# 02_FPGA-jtag.net
KiCad netlist of a schematic drawn in Altium Designer
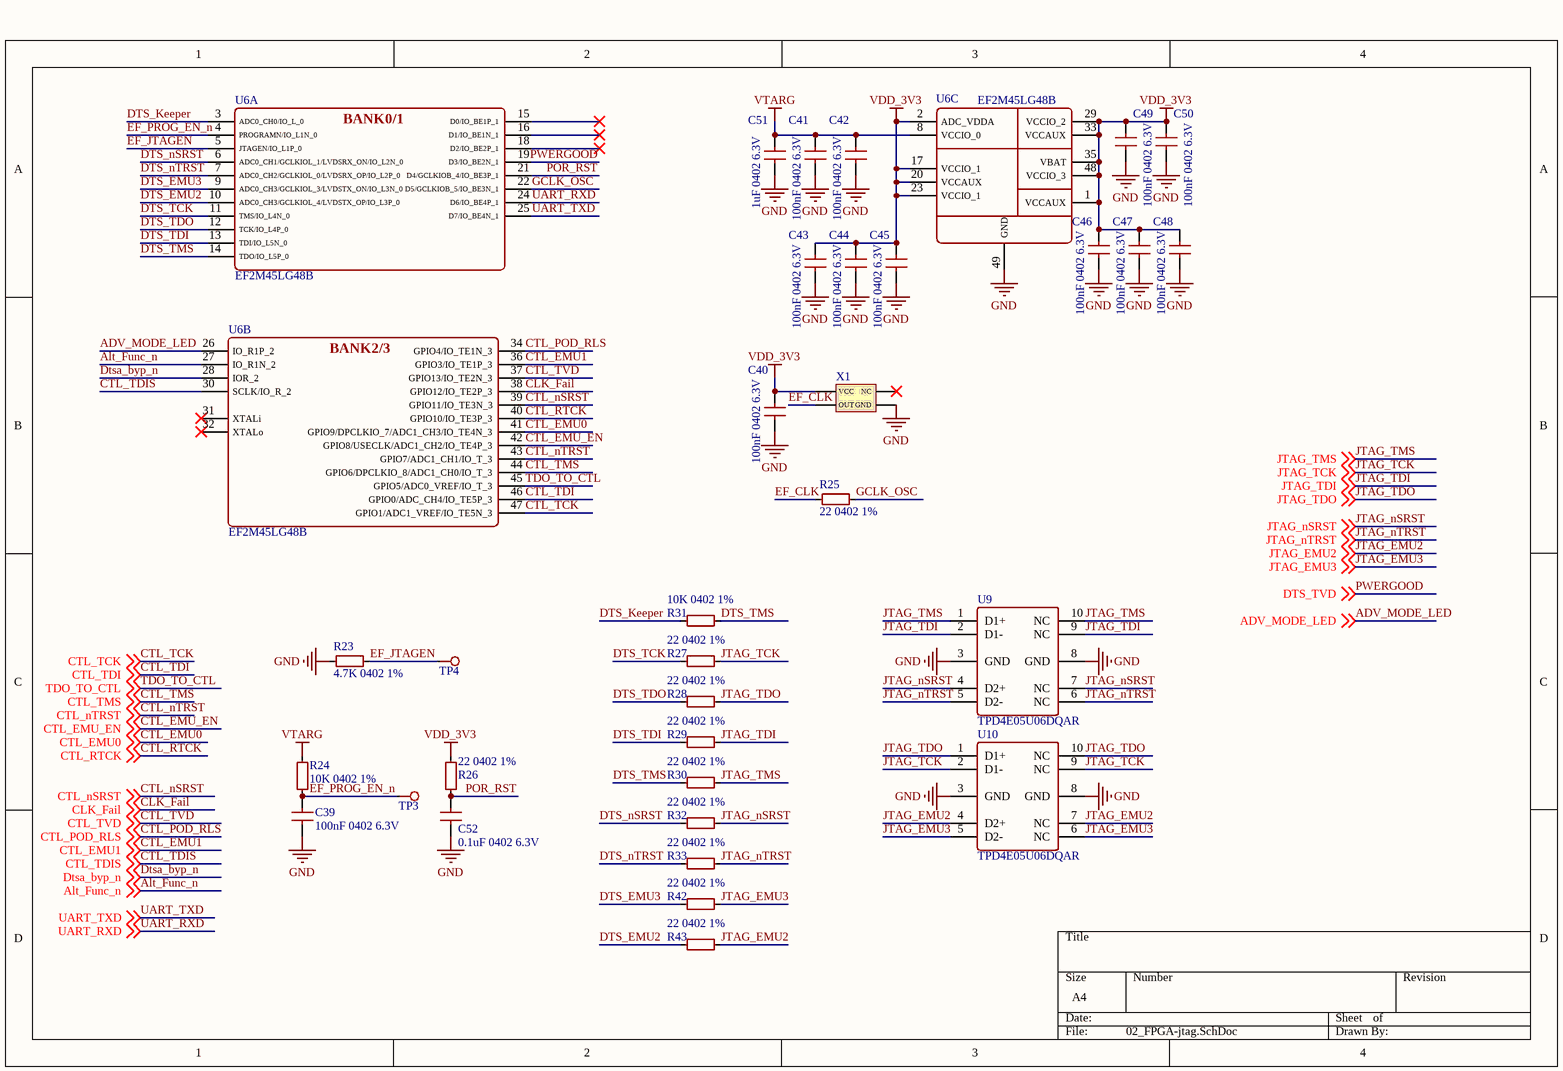
[diagram p0: 02_FPGA-jtag.SchDoc]

(export (version "E")
  (design (tool "Eeschema 10.0.6"))
  (components
    (comp (ref "C39")
      (value "100nF 0402 6.3V")
      (footprint "C_0402_1005Metric")
      (description "Unpolarized capacitor")
      (libsource (lib "FPGA_VGA") (part "C"))
    )
    (comp (ref "C40")
      (value "100nF 0402 6.3V")
      (footprint "C_0402_1005Metric")
      (description "Unpolarized capacitor")
      (libsource (lib "FPGA_VGA") (part "C"))
    )
    (comp (ref "C41")
      (value "100nF 0402 6.3V")
      (footprint "C_0402_1005Metric")
      (description "Unpolarized capacitor")
      (libsource (lib "FPGA_VGA") (part "C"))
    )
    (comp (ref "C42")
      (value "100nF 0402 6.3V")
      (footprint "C_0402_1005Metric")
      (description "Unpolarized capacitor")
      (libsource (lib "FPGA_VGA") (part "C"))
    )
    (comp (ref "C43")
      (value "100nF 0402 6.3V")
      (footprint "C_0402_1005Metric")
      (description "Unpolarized capacitor")
      (libsource (lib "FPGA_VGA") (part "C"))
    )
    (comp (ref "C44")
      (value "100nF 0402 6.3V")
      (footprint "C_0402_1005Metric")
      (description "Unpolarized capacitor")
      (libsource (lib "FPGA_VGA") (part "C"))
    )
    (comp (ref "C45")
      (value "100nF 0402 6.3V")
      (footprint "C_0402_1005Metric")
      (description "Unpolarized capacitor")
      (libsource (lib "FPGA_VGA") (part "C"))
    )
    (comp (ref "C46")
      (value "100nF 0402 6.3V")
      (footprint "C_0402_1005Metric")
      (description "Unpolarized capacitor")
      (libsource (lib "FPGA_VGA") (part "C"))
    )
    (comp (ref "C47")
      (value "100nF 0402 6.3V")
      (footprint "C_0402_1005Metric")
      (description "Unpolarized capacitor")
      (libsource (lib "FPGA_VGA") (part "C"))
    )
    (comp (ref "C48")
      (value "100nF 0402 6.3V")
      (footprint "C_0402_1005Metric")
      (description "Unpolarized capacitor")
      (libsource (lib "FPGA_VGA") (part "C"))
    )
    (comp (ref "C49")
      (value "100nF 0402 6.3V")
      (footprint "C_0402_1005Metric")
      (description "Unpolarized capacitor")
      (libsource (lib "FPGA_VGA") (part "C"))
    )
    (comp (ref "C50")
      (value "100nF 0402 6.3V")
      (footprint "C_0402_1005Metric")
      (description "Unpolarized capacitor")
      (libsource (lib "FPGA_VGA") (part "C"))
    )
    (comp (ref "C51")
      (value "1uF 0402 6.3V")
      (footprint "C_0402_1005Metric")
      (description "Unpolarized capacitor")
      (libsource (lib "FPGA_VGA") (part "C"))
    )
    (comp (ref "C52")
      (value "0.1uF 0402 6.3V")
      (footprint "C_0402_1005Metric")
      (description "Unpolarized capacitor")
      (libsource (lib "FPGA_VGA") (part "C"))
    )
    (comp (ref "R23")
      (value "4.7K 0402 1%")
      (footprint "R_0402_1005Metric")
      (description "Resistor")
      (libsource (lib "FPGA_VGA") (part "R"))
    )
    (comp (ref "R24")
      (value "10K 0402 1%")
      (footprint "R_0402_1005Metric")
      (description "Resistor")
      (libsource (lib "FPGA_VGA") (part "R"))
    )
    (comp (ref "R25")
      (value "22 0402 1%")
      (footprint "R_0402_1005Metric")
      (description "Resistor")
      (libsource (lib "FPGA_VGA") (part "R"))
    )
    (comp (ref "R26")
      (value "22 0402 1%")
      (footprint "R_0402_1005Metric")
      (description "Resistor")
      (libsource (lib "FPGA_VGA") (part "R"))
    )
    (comp (ref "R27")
      (value "22 0402 1%")
      (footprint "R_0402_1005Metric")
      (description "Resistor")
      (libsource (lib "FPGA_VGA") (part "R"))
    )
    (comp (ref "R28")
      (value "22 0402 1%")
      (footprint "R_0402_1005Metric")
      (description "Resistor")
      (libsource (lib "FPGA_VGA") (part "R"))
    )
    (comp (ref "R29")
      (value "22 0402 1%")
      (footprint "R_0402_1005Metric")
      (description "Resistor")
      (libsource (lib "FPGA_VGA") (part "R"))
    )
    (comp (ref "R30")
      (value "22 0402 1%")
      (footprint "R_0402_1005Metric")
      (description "Resistor")
      (libsource (lib "FPGA_VGA") (part "R"))
    )
    (comp (ref "R31")
      (value "10K 0402 1%")
      (footprint "R_0402_1005Metric")
      (description "Resistor")
      (libsource (lib "FPGA_VGA") (part "R"))
    )
    (comp (ref "R32")
      (value "22 0402 1%")
      (footprint "R_0402_1005Metric")
      (description "Resistor")
      (libsource (lib "FPGA_VGA") (part "R"))
    )
    (comp (ref "R33")
      (value "22 0402 1%")
      (footprint "R_0402_1005Metric")
      (description "Resistor")
      (libsource (lib "FPGA_VGA") (part "R"))
    )
    (comp (ref "R42")
      (value "22 0402 1%")
      (footprint "R_0402_1005Metric")
      (description "Resistor")
      (libsource (lib "FPGA_VGA") (part "R"))
    )
    (comp (ref "R43")
      (value "22 0402 1%")
      (footprint "R_0402_1005Metric")
      (description "Resistor")
      (libsource (lib "FPGA_VGA") (part "R"))
    )
    (comp (ref "TP3")
      (value "TestPoint")
      (footprint "TP-60MIL")
      (description "test point tp")
      (libsource (lib "FPGA_FTX232HL") (part "TestPoint"))
    )
    (comp (ref "TP4")
      (value "TestPoint")
      (footprint "TP-60MIL")
      (description "test point tp")
      (libsource (lib "FPGA_FTX232HL") (part "TestPoint"))
    )
    (comp (ref "U6")
      (value "EF2M45LG48B")
      (footprint "EF2M45_LQFP-48L")
      (description "SALELF® 2 系列 FPGA")
      (libsource (lib "XDS100V3-anlogic") (part "EF2M45LG48B"))
    )
    (comp (ref "U9")
      (value "TPD4E05U06DQAR")
      (footprint "TPD4E05U06DQAR")
      (description "No Description Available")
      (fields (field (name "MANUFACTURER") "Texas Instruments"))
      (libsource (lib "XDS100V3-anlogic") (part "TPD4E05U06DQAR"))
    )
    (comp (ref "U10")
      (value "TPD4E05U06DQAR")
      (footprint "TPD4E05U06DQAR")
      (description "No Description Available")
      (fields (field (name "MANUFACTURER") "Texas Instruments"))
      (libsource (lib "XDS100V3-anlogic") (part "TPD4E05U06DQAR"))
    )
    (comp (ref "X1")
      (value "Crystal-4Pin-Active-GND2-NC1")
      (footprint "Crystal-Active_SMD_3225-4Pin_3.2x2.5mm")
      (description "4 pin crystal,1 for NC,2 for GND")
      (libsource (lib "XDS100V3-anlogic") (part "Crystal-4Pin-Active-GND2-NC1"))
    )
  )
  (nets
    (net (code "1") (name "/DTS_EMU2") (class "Default")
      (node (ref "R43") (pin "2") (pinfunction "2_2") (pintype "passive"))
      (node (ref "U6") (pin "10") (pinfunction "ADC0_CH3/GCLKIOL_4/LVDSTX_OP/IO_L3P_0_10") (pintype "passive"))
    )
    (net (code "2") (name "/DTS_EMU3") (class "Default")
      (node (ref "R42") (pin "2") (pinfunction "2_2") (pintype "passive"))
      (node (ref "U6") (pin "9") (pinfunction "ADC0_CH3/GCLKIOL_3/LVDSTX_ON/IO_L3N_0_9") (pintype "passive"))
    )
    (net (code "3") (name "/DTS_Keeper") (class "Default")
      (node (ref "R31") (pin "2") (pinfunction "2_2") (pintype "passive"))
      (node (ref "U6") (pin "3") (pinfunction "ADC0_CH0/IO_L_0_3") (pintype "passive"))
    )
    (net (code "4") (name "/DTS_TCK") (class "Default")
      (node (ref "R27") (pin "2") (pinfunction "2_2") (pintype "passive"))
      (node (ref "U6") (pin "11") (pinfunction "TMS/IO_L4N_0_11") (pintype "passive"))
    )
    (net (code "5") (name "/DTS_TDI") (class "Default")
      (node (ref "R29") (pin "2") (pinfunction "2_2") (pintype "passive"))
      (node (ref "U6") (pin "13") (pinfunction "TDI/IO_L5N_0_13") (pintype "passive"))
    )
    (net (code "6") (name "/DTS_TDO") (class "Default")
      (node (ref "R28") (pin "2") (pinfunction "2_2") (pintype "passive"))
      (node (ref "U6") (pin "12") (pinfunction "TCK/IO_L4P_0_12") (pintype "passive"))
    )
    (net (code "7") (name "/DTS_TMS") (class "Default")
      (node (ref "R30") (pin "2") (pinfunction "2_2") (pintype "passive"))
      (node (ref "R31") (pin "1") (pinfunction "1_1") (pintype "passive"))
      (node (ref "U6") (pin "14") (pinfunction "TDO/IO_L5P_0_14") (pintype "passive"))
    )
    (net (code "8") (name "/DTS_nSRST") (class "Default")
      (node (ref "R32") (pin "2") (pinfunction "2_2") (pintype "passive"))
      (node (ref "U6") (pin "6") (pinfunction "ADC0_CH1/GCLKIOL_1/LVDSRX_ON/IO_L2N_0_6") (pintype "passive"))
    )
    (net (code "9") (name "/DTS_nTRST") (class "Default")
      (node (ref "R33") (pin "2") (pinfunction "2_2") (pintype "passive"))
      (node (ref "U6") (pin "7") (pinfunction "ADC0_CH2/GCLKIOL_0/LVDSRX_OP/IO_L2P_0_7") (pintype "passive"))
    )
    (net (code "10") (name "/EF_CLK") (class "Default")
      (node (ref "R25") (pin "1") (pinfunction "1_1") (pintype "passive"))
      (node (ref "X1") (pin "3") (pinfunction "OUT_3") (pintype "passive"))
    )
    (net (code "11") (name "/EF_JTAGEN") (class "Default")
      (node (ref "R23") (pin "1") (pinfunction "1_1") (pintype "passive"))
      (node (ref "TP4") (pin "1") (pinfunction "1_1") (pintype "passive"))
      (node (ref "U6") (pin "5") (pinfunction "JTAGEN/IO_L1P_0_5") (pintype "passive"))
    )
    (net (code "12") (name "/EF_PROG_EN_n") (class "Default")
      (node (ref "C39") (pin "2") (pinfunction "2_2") (pintype "passive"))
      (node (ref "R24") (pin "2") (pinfunction "2_2") (pintype "passive"))
      (node (ref "TP3") (pin "1") (pinfunction "1_1") (pintype "passive"))
      (node (ref "U6") (pin "4") (pinfunction "PROGRAMN/IO_L1N_0_4") (pintype "passive"))
    )
    (net (code "13") (name "/GCLK_OSC") (class "Default")
      (node (ref "R25") (pin "2") (pinfunction "2_2") (pintype "passive"))
      (node (ref "U6") (pin "22") (pinfunction "D5/GCLKIOB_5/IO_BE3N_1_22") (pintype "passive"))
    )
    (net (code "14") (name "/POR_RST") (class "Default")
      (node (ref "C52") (pin "1") (pinfunction "1_1") (pintype "passive"))
      (node (ref "R26") (pin "1") (pinfunction "1_1") (pintype "passive"))
      (node (ref "U6") (pin "21") (pinfunction "D4/GCLKIOB_4/IO_BE3P_1_21") (pintype "passive"))
    )
    (net (code "15") (name "ADV_MODE_LED") (class "Default")
      (node (ref "U6") (pin "26") (pinfunction "IO_R1P_2_26") (pintype "passive"))
    )
    (net (code "16") (name "Alt_Func_n") (class "Default")
      (node (ref "U6") (pin "27") (pinfunction "IO_R1N_2_27") (pintype "passive"))
    )
    (net (code "17") (name "CLK_Fail") (class "Default")
      (node (ref "U6") (pin "38") (pinfunction "GPIO12/IO_TE2P_3_38") (pintype "passive"))
    )
    (net (code "18") (name "CTL_EMU0") (class "Default")
      (node (ref "U6") (pin "41") (pinfunction "GPIO9/DPCLKIO_7/ADC1_CH3/IO_TE4N_3_41") (pintype "passive"))
    )
    (net (code "19") (name "CTL_EMU1") (class "Default")
      (node (ref "U6") (pin "36") (pinfunction "GPIO3/IO_TE1P_3_36") (pintype "passive"))
    )
    (net (code "20") (name "CTL_EMU_EN") (class "Default")
      (node (ref "U6") (pin "42") (pinfunction "GPIO8/USECLK/ADC1_CH2/IO_TE4P_3_42") (pintype "passive"))
    )
    (net (code "21") (name "CTL_POD_RLS") (class "Default")
      (node (ref "U6") (pin "34") (pinfunction "GPIO4/IO_TE1N_3_34") (pintype "passive"))
    )
    (net (code "22") (name "CTL_RTCK") (class "Default")
      (node (ref "U6") (pin "40") (pinfunction "GPIO10/IO_TE3P_3_40") (pintype "passive"))
    )
    (net (code "23") (name "CTL_TCK") (class "Default")
      (node (ref "U6") (pin "47") (pinfunction "GPIO1/ADC1_VREF/IO_TE5N_3_47") (pintype "passive"))
    )
    (net (code "24") (name "CTL_TDI") (class "Default")
      (node (ref "U6") (pin "46") (pinfunction "GPIO0/ADC_CH4/IO_TE5P_3_46") (pintype "passive"))
    )
    (net (code "25") (name "CTL_TDIS") (class "Default")
      (node (ref "U6") (pin "30") (pinfunction "SCLK/IO_R_2_30") (pintype "passive"))
    )
    (net (code "26") (name "CTL_TMS") (class "Default")
      (node (ref "U6") (pin "44") (pinfunction "GPIO6/DPCLKIO_8/ADC1_CH0/IO_T_3_44") (pintype "passive"))
    )
    (net (code "27") (name "CTL_TVD") (class "Default")
      (node (ref "U6") (pin "37") (pinfunction "GPIO13/IO_TE2N_3_37") (pintype "passive"))
    )
    (net (code "28") (name "CTL_nSRST") (class "Default")
      (node (ref "U6") (pin "39") (pinfunction "GPIO11/IO_TE3N_3_39") (pintype "passive"))
    )
    (net (code "29") (name "CTL_nTRST") (class "Default")
      (node (ref "U6") (pin "43") (pinfunction "GPIO7/ADC1_CH1/IO_T_3_43") (pintype "passive"))
    )
    (net (code "30") (name "DTS_TVD") (class "Default")
      (node (ref "U6") (pin "19") (pinfunction "D3/IO_BE2N_1_19") (pintype "passive"))
    )
    (net (code "31") (name "Dtsa_byp_n") (class "Default")
      (node (ref "U6") (pin "28") (pinfunction "IOR_2_28") (pintype "passive"))
    )
    (net (code "32") (name "GND") (class "Default")
      (node (ref "C39") (pin "1") (pinfunction "1_1") (pintype "passive"))
      (node (ref "C40") (pin "2") (pinfunction "2_2") (pintype "passive"))
      (node (ref "C41") (pin "2") (pinfunction "2_2") (pintype "passive"))
      (node (ref "C42") (pin "2") (pinfunction "2_2") (pintype "passive"))
      (node (ref "C43") (pin "2") (pinfunction "2_2") (pintype "passive"))
      (node (ref "C44") (pin "2") (pinfunction "2_2") (pintype "passive"))
      (node (ref "C45") (pin "2") (pinfunction "2_2") (pintype "passive"))
      (node (ref "C46") (pin "2") (pinfunction "2_2") (pintype "passive"))
      (node (ref "C47") (pin "2") (pinfunction "2_2") (pintype "passive"))
      (node (ref "C48") (pin "2") (pinfunction "2_2") (pintype "passive"))
      (node (ref "C49") (pin "2") (pinfunction "2_2") (pintype "passive"))
      (node (ref "C50") (pin "2") (pinfunction "2_2") (pintype "passive"))
      (node (ref "C51") (pin "2") (pinfunction "2_2") (pintype "passive"))
      (node (ref "C52") (pin "2") (pinfunction "2_2") (pintype "passive"))
      (node (ref "R23") (pin "2") (pinfunction "2_2") (pintype "passive"))
      (node (ref "U10") (pin "3") (pinfunction "GND_3") (pintype "passive"))
      (node (ref "U10") (pin "8") (pinfunction "GND_8") (pintype "power_in"))
      (node (ref "U6") (pin "49") (pinfunction "GND_49") (pintype "passive"))
      (node (ref "U9") (pin "3") (pinfunction "GND_3") (pintype "passive"))
      (node (ref "U9") (pin "8") (pinfunction "GND_8") (pintype "power_in"))
      (node (ref "X1") (pin "2") (pinfunction "GND_2") (pintype "passive"))
    )
    (net (code "33") (name "JTAG_EMU2") (class "Default")
      (node (ref "R43") (pin "1") (pinfunction "1_1") (pintype "passive"))
      (node (ref "U10") (pin "4") (pinfunction "D2+_4") (pintype "passive"))
      (node (ref "U10") (pin "7") (pinfunction "NC_7") (pintype "passive"))
    )
    (net (code "34") (name "JTAG_EMU3") (class "Default")
      (node (ref "R42") (pin "1") (pinfunction "1_1") (pintype "passive"))
      (node (ref "U10") (pin "5") (pinfunction "D2-_5") (pintype "passive"))
      (node (ref "U10") (pin "6") (pinfunction "NC_6") (pintype "passive"))
    )
    (net (code "35") (name "JTAG_TCK") (class "Default")
      (node (ref "R27") (pin "1") (pinfunction "1_1") (pintype "passive"))
      (node (ref "U10") (pin "2") (pinfunction "D1-_2") (pintype "passive"))
      (node (ref "U10") (pin "9") (pinfunction "NC_9") (pintype "passive"))
    )
    (net (code "36") (name "JTAG_TDI") (class "Default")
      (node (ref "R29") (pin "1") (pinfunction "1_1") (pintype "passive"))
      (node (ref "U9") (pin "2") (pinfunction "D1-_2") (pintype "passive"))
      (node (ref "U9") (pin "9") (pinfunction "NC_9") (pintype "passive"))
    )
    (net (code "37") (name "JTAG_TDO") (class "Default")
      (node (ref "R28") (pin "1") (pinfunction "1_1") (pintype "passive"))
      (node (ref "U10") (pin "1") (pinfunction "D1+_1") (pintype "passive"))
      (node (ref "U10") (pin "10") (pinfunction "NC_10") (pintype "passive"))
    )
    (net (code "38") (name "JTAG_TMS") (class "Default")
      (node (ref "R30") (pin "1") (pinfunction "1_1") (pintype "passive"))
      (node (ref "U9") (pin "1") (pinfunction "D1+_1") (pintype "passive"))
      (node (ref "U9") (pin "10") (pinfunction "NC_10") (pintype "passive"))
    )
    (net (code "39") (name "JTAG_nSRST") (class "Default")
      (node (ref "R32") (pin "1") (pinfunction "1_1") (pintype "passive"))
      (node (ref "U9") (pin "4") (pinfunction "D2+_4") (pintype "passive"))
      (node (ref "U9") (pin "7") (pinfunction "NC_7") (pintype "passive"))
    )
    (net (code "40") (name "JTAG_nTRST") (class "Default")
      (node (ref "R33") (pin "1") (pinfunction "1_1") (pintype "passive"))
      (node (ref "U9") (pin "5") (pinfunction "D2-_5") (pintype "passive"))
      (node (ref "U9") (pin "6") (pinfunction "NC_6") (pintype "passive"))
    )
    (net (code "41") (name "TDO_TO_CTL") (class "Default")
      (node (ref "U6") (pin "45") (pinfunction "GPIO5/ADC0_VREF/IO_T_3_45") (pintype "passive"))
    )
    (net (code "42") (name "UART_RXD") (class "Default")
      (node (ref "U6") (pin "24") (pinfunction "D6/IO_BE4P_1_24") (pintype "passive"))
    )
    (net (code "43") (name "UART_TXD") (class "Default")
      (node (ref "U6") (pin "25") (pinfunction "D7/IO_BE4N_1_25") (pintype "passive"))
    )
    (net (code "44") (name "VDD_3V3") (class "Default")
      (node (ref "C40") (pin "1") (pinfunction "1_1") (pintype "passive"))
      (node (ref "C43") (pin "1") (pinfunction "1_1") (pintype "passive"))
      (node (ref "C44") (pin "1") (pinfunction "1_1") (pintype "passive"))
      (node (ref "C45") (pin "1") (pinfunction "1_1") (pintype "passive"))
      (node (ref "C46") (pin "1") (pinfunction "1_1") (pintype "passive"))
      (node (ref "C47") (pin "1") (pinfunction "1_1") (pintype "passive"))
      (node (ref "C48") (pin "1") (pinfunction "1_1") (pintype "passive"))
      (node (ref "C49") (pin "1") (pinfunction "1_1") (pintype "passive"))
      (node (ref "C50") (pin "1") (pinfunction "1_1") (pintype "passive"))
      (node (ref "R26") (pin "2") (pinfunction "2_2") (pintype "passive"))
      (node (ref "U6") (pin "1") (pinfunction "VCCAUX_1") (pintype "passive"))
      (node (ref "U6") (pin "17") (pinfunction "VCCIO_1_17") (pintype "passive"))
      (node (ref "U6") (pin "2") (pinfunction "ADC_VDDA_2") (pintype "passive"))
      (node (ref "U6") (pin "20") (pinfunction "VCCAUX_20") (pintype "passive"))
      (node (ref "U6") (pin "23") (pinfunction "VCCIO_1_23") (pintype "passive"))
      (node (ref "U6") (pin "29") (pinfunction "VCCIO_2_29") (pintype "passive"))
      (node (ref "U6") (pin "33") (pinfunction "VCCAUX_33") (pintype "passive"))
      (node (ref "U6") (pin "35") (pinfunction "VBAT_35") (pintype "passive"))
      (node (ref "U6") (pin "48") (pinfunction "VCCIO_3_48") (pintype "passive"))
      (node (ref "X1") (pin "4") (pinfunction "VCC_4") (pintype "passive"))
    )
    (net (code "45") (name "VTARG") (class "Default")
      (node (ref "C41") (pin "1") (pinfunction "1_1") (pintype "passive"))
      (node (ref "C42") (pin "1") (pinfunction "1_1") (pintype "passive"))
      (node (ref "C51") (pin "1") (pinfunction "1_1") (pintype "passive"))
      (node (ref "R24") (pin "1") (pinfunction "1_1") (pintype "passive"))
      (node (ref "U6") (pin "8") (pinfunction "VCCIO_0_8") (pintype "passive"))
    )
    (net (code "46") (name "unconnected-(U6A-D0{slash}IO_BE1P_1-Pad15)") (class "Default")
      (node (ref "U6") (pin "15") (pinfunction "D0/IO_BE1P_1_15") (pintype "passive+no_connect"))
    )
    (net (code "47") (name "unconnected-(U6A-D1{slash}IO_BE1N_1-Pad16)") (class "Default")
      (node (ref "U6") (pin "16") (pinfunction "D1/IO_BE1N_1_16") (pintype "passive+no_connect"))
    )
    (net (code "48") (name "unconnected-(U6A-D2{slash}IO_BE2P_1-Pad18)") (class "Default")
      (node (ref "U6") (pin "18") (pinfunction "D2/IO_BE2P_1_18") (pintype "passive+no_connect"))
    )
    (net (code "49") (name "unconnected-(U6B-XTALi-Pad31)") (class "Default")
      (node (ref "U6") (pin "31") (pinfunction "XTALi_31") (pintype "passive+no_connect"))
    )
    (net (code "50") (name "unconnected-(U6B-XTALo-Pad32)") (class "Default")
      (node (ref "U6") (pin "32") (pinfunction "XTALo_32") (pintype "passive+no_connect"))
    )
    (net (code "51") (name "unconnected-(X1-NC-Pad1)") (class "Default")
      (node (ref "X1") (pin "1") (pinfunction "NC_1") (pintype "passive+no_connect"))
    )
  )
)
